# bq25570_board_large.net
KiCad netlist of a schematic drawn in EAGLE
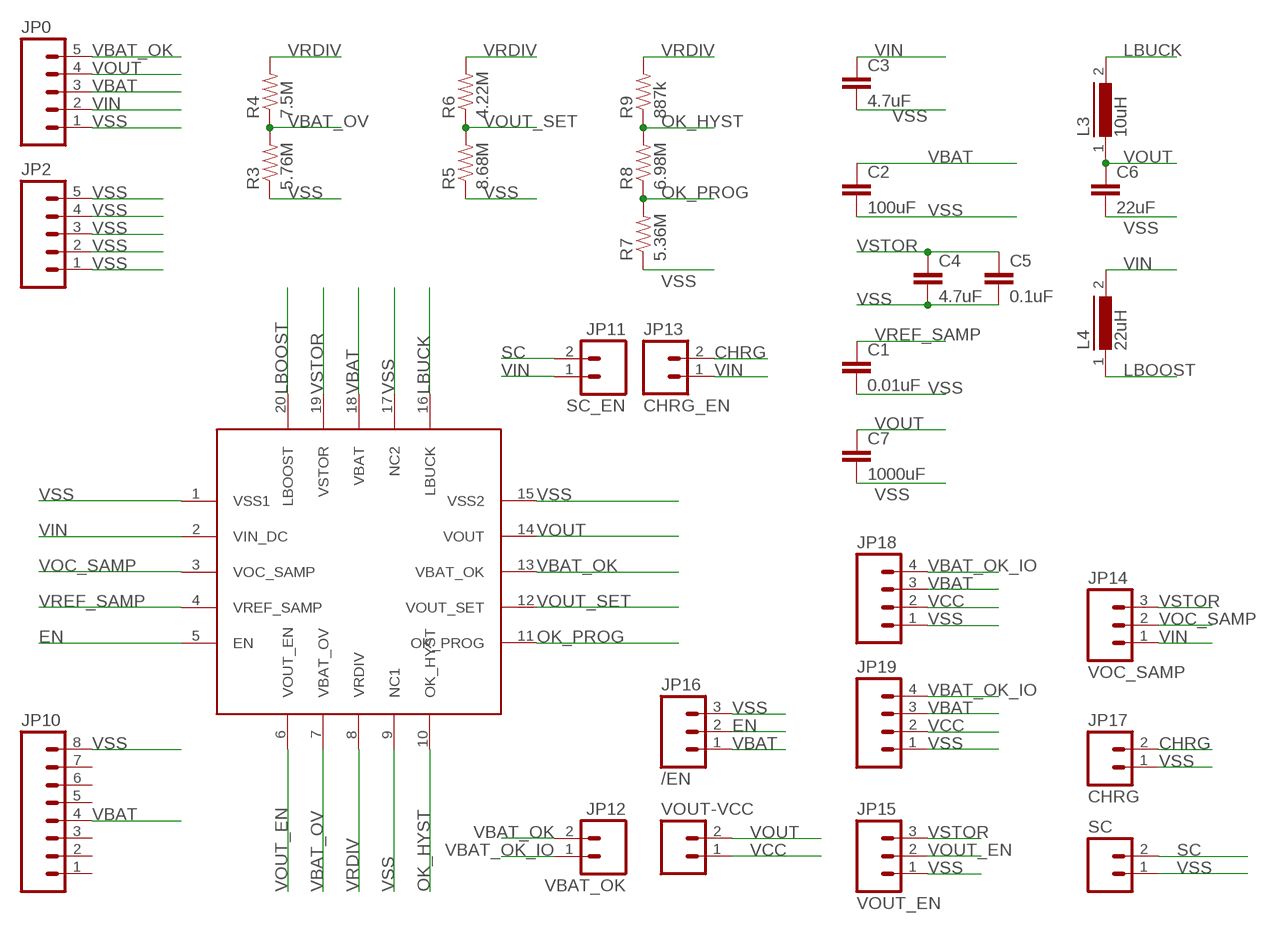
[diagram p0: schematic, sheet 1]

(export (version "E")
  (design (tool "Eeschema 10.0.6"))
  (components
    (comp (ref "C1")
      (value "0.01uF")
      (footprint "eagle-import:CAP-PTH-SMALLEZ")
      (libsource (lib "eagle-import") (part "CAPEZ"))
    )
    (comp (ref "C2")
      (value "100uF")
      (footprint "eagle-import:CAP-PTH-SMALLEZ")
      (libsource (lib "eagle-import") (part "CAPEZ"))
    )
    (comp (ref "C3")
      (value "4.7uF")
      (footprint "eagle-import:CAP-PTH-SMALLEZ")
      (libsource (lib "eagle-import") (part "CAPEZ"))
    )
    (comp (ref "C4")
      (value "4.7uF")
      (footprint "eagle-import:CAP-PTH-SMALLEZ")
      (libsource (lib "eagle-import") (part "CAPEZ"))
    )
    (comp (ref "C5")
      (value "0.1uF")
      (footprint "eagle-import:CAP-PTH-SMALLEZ")
      (libsource (lib "eagle-import") (part "CAPEZ"))
    )
    (comp (ref "C6")
      (value "22uF")
      (footprint "eagle-import:CAP-PTH-SMALLEZ")
      (libsource (lib "eagle-import") (part "CAPEZ"))
    )
    (comp (ref "C7")
      (value "1000uF")
      (footprint "eagle-import:CAP-PTH-SMALLEZ")
      (libsource (lib "eagle-import") (part "CAPEZ"))
    )
    (comp (ref "JP0")
      (value "M05PTH")
      (footprint "eagle-import:1X05")
      (libsource (lib "eagle-import") (part "M05PTH"))
    )
    (comp (ref "JP2")
      (value "M05PTH")
      (footprint "eagle-import:1X05")
      (libsource (lib "eagle-import") (part "M05PTH"))
    )
    (comp (ref "JP10")
      (value "M08")
      (footprint "eagle-import:1X08_ROUND")
      (libsource (lib "eagle-import") (part "M08"))
    )
    (comp (ref "JP11")
      (value "SC_EN")
      (footprint "eagle-import:1X02")
      (libsource (lib "eagle-import") (part "M02PTH"))
    )
    (comp (ref "JP12")
      (value "VBAT_OK")
      (footprint "eagle-import:1X02")
      (libsource (lib "eagle-import") (part "M02PTH"))
    )
    (comp (ref "JP13")
      (value "CHRG_EN")
      (footprint "eagle-import:1X02")
      (libsource (lib "eagle-import") (part "M02PTH"))
    )
    (comp (ref "JP14")
      (value "VOC_SAMP")
      (footprint "eagle-import:1X03")
      (libsource (lib "eagle-import") (part "M03PTH"))
    )
    (comp (ref "JP15")
      (value "VOUT_EN")
      (footprint "eagle-import:1X03")
      (libsource (lib "eagle-import") (part "M03PTH"))
    )
    (comp (ref "JP16")
      (value "/EN")
      (footprint "eagle-import:1X03")
      (libsource (lib "eagle-import") (part "M03PTH"))
    )
    (comp (ref "JP17")
      (value "CHRG")
      (footprint "eagle-import:1X02")
      (libsource (lib "eagle-import") (part "M02PTH"))
    )
    (comp (ref "JP18")
      (value "M04PTH")
      (footprint "eagle-import:1X04")
      (libsource (lib "eagle-import") (part "M04PTH"))
    )
    (comp (ref "JP19")
      (value "M04PTH")
      (footprint "eagle-import:1X04")
      (libsource (lib "eagle-import") (part "M04PTH"))
    )
    (comp (ref "L3")
      (value "10uH")
      (footprint "eagle-import:BC12")
      (libsource (lib "eagle-import") (part "BC12"))
    )
    (comp (ref "L4")
      (value "22uH")
      (footprint "eagle-import:BC12")
      (libsource (lib "eagle-import") (part "BC12"))
    )
    (comp (ref "R3")
      (value "5.76M")
      (footprint "eagle-import:AXIAL-0.3")
      (libsource (lib "eagle-import") (part "1KOHM-1/4W-1%(PTH)"))
    )
    (comp (ref "R4")
      (value "7.5M")
      (footprint "eagle-import:AXIAL-0.3")
      (libsource (lib "eagle-import") (part "1KOHM-1/4W-1%(PTH)"))
    )
    (comp (ref "R5")
      (value "8.68M")
      (footprint "eagle-import:AXIAL-0.3")
      (libsource (lib "eagle-import") (part "1KOHM-1/4W-1%(PTH)"))
    )
    (comp (ref "R6")
      (value "4.22M")
      (footprint "eagle-import:AXIAL-0.3")
      (libsource (lib "eagle-import") (part "1KOHM-1/4W-1%(PTH)"))
    )
    (comp (ref "R7")
      (value "5.36M")
      (footprint "eagle-import:AXIAL-0.3")
      (libsource (lib "eagle-import") (part "1KOHM-1/4W-1%(PTH)"))
    )
    (comp (ref "R8")
      (value "6.98M")
      (footprint "eagle-import:AXIAL-0.3")
      (libsource (lib "eagle-import") (part "1KOHM-1/4W-1%(PTH)"))
    )
    (comp (ref "R9")
      (value "887k")
      (footprint "eagle-import:AXIAL-0.3")
      (libsource (lib "eagle-import") (part "1KOHM-1/4W-1%(PTH)"))
    )
    (comp (ref "SC")
      (value "M02PTH")
      (footprint "eagle-import:1X02")
      (libsource (lib "eagle-import") (part "M02PTH"))
    )
    (comp (ref "SV2")
      (value "BQ25570_BOARD")
      (footprint "eagle-import:MA05-1")
      (libsource (lib "eagle-import") (part "BQ25570_BOARD"))
    )
    (comp (ref "VOUT-VCC")
      (value "M02PTH")
      (footprint "eagle-import:1X02")
      (libsource (lib "eagle-import") (part "M02PTH"))
    )
  )
  (nets
    (net (code "1") (name "/CHRG") (class "Default")
      (node (ref "JP13") (pin "2") (pinfunction "2_2") (pintype "passive"))
      (node (ref "JP17") (pin "2") (pinfunction "2_2") (pintype "passive"))
    )
    (net (code "2") (name "/EN") (class "Default")
      (node (ref "JP16") (pin "2") (pinfunction "2_2") (pintype "passive"))
      (node (ref "SV2") (pin "5") (pinfunction "EN_5") (pintype "bidirectional"))
    )
    (net (code "3") (name "/LBOOST") (class "Default")
      (node (ref "L4") (pin "1") (pinfunction "1_1") (pintype "passive"))
      (node (ref "SV2") (pin "20") (pinfunction "LBOOST_20") (pintype "bidirectional"))
    )
    (net (code "4") (name "/LBUCK") (class "Default")
      (node (ref "L3") (pin "2") (pinfunction "2_2") (pintype "passive"))
      (node (ref "SV2") (pin "16") (pinfunction "LBUCK_16") (pintype "bidirectional"))
    )
    (net (code "5") (name "/OK_HYST") (class "Default")
      (node (ref "R8") (pin "P$2") (pinfunction "2_P$2") (pintype "passive"))
      (node (ref "R9") (pin "P$1") (pinfunction "1_P$1") (pintype "passive"))
      (node (ref "SV2") (pin "10") (pinfunction "OK_HYST_10") (pintype "bidirectional"))
    )
    (net (code "6") (name "/OK_PROG") (class "Default")
      (node (ref "R7") (pin "P$2") (pinfunction "2_P$2") (pintype "passive"))
      (node (ref "R8") (pin "P$1") (pinfunction "1_P$1") (pintype "passive"))
      (node (ref "SV2") (pin "11") (pinfunction "OK_PROG_11") (pintype "bidirectional"))
    )
    (net (code "7") (name "/SC") (class "Default")
      (node (ref "JP11") (pin "2") (pinfunction "2_2") (pintype "passive"))
      (node (ref "SC") (pin "2") (pinfunction "2_2") (pintype "passive"))
    )
    (net (code "8") (name "/VBAT") (class "Default")
      (node (ref "C2") (pin "1") (pinfunction "1_1") (pintype "passive"))
      (node (ref "JP0") (pin "3") (pinfunction "3_3") (pintype "passive"))
      (node (ref "JP10") (pin "4") (pinfunction "4_4") (pintype "passive"))
      (node (ref "JP16") (pin "1") (pinfunction "1_1") (pintype "passive"))
      (node (ref "JP18") (pin "3") (pinfunction "3_3") (pintype "passive"))
      (node (ref "JP19") (pin "3") (pinfunction "3_3") (pintype "passive"))
      (node (ref "SV2") (pin "18") (pinfunction "VBAT_18") (pintype "bidirectional"))
    )
    (net (code "9") (name "/VBAT_OK") (class "Default")
      (node (ref "JP0") (pin "5") (pinfunction "5_5") (pintype "passive"))
      (node (ref "JP12") (pin "2") (pinfunction "2_2") (pintype "passive"))
      (node (ref "SV2") (pin "13") (pinfunction "VBAT_OK_13") (pintype "bidirectional"))
    )
    (net (code "10") (name "/VBAT_OK_IO") (class "Default")
      (node (ref "JP12") (pin "1") (pinfunction "1_1") (pintype "passive"))
      (node (ref "JP18") (pin "4") (pinfunction "4_4") (pintype "passive"))
      (node (ref "JP19") (pin "4") (pinfunction "4_4") (pintype "passive"))
    )
    (net (code "11") (name "/VBAT_OV") (class "Default")
      (node (ref "R3") (pin "P$2") (pinfunction "2_P$2") (pintype "passive"))
      (node (ref "R4") (pin "P$1") (pinfunction "1_P$1") (pintype "passive"))
      (node (ref "SV2") (pin "7") (pinfunction "VBAT_OV_7") (pintype "bidirectional"))
    )
    (net (code "12") (name "/VCC") (class "Default")
      (node (ref "JP18") (pin "2") (pinfunction "2_2") (pintype "passive"))
      (node (ref "JP19") (pin "2") (pinfunction "2_2") (pintype "passive"))
      (node (ref "VOUT-VCC") (pin "1") (pinfunction "1_1") (pintype "passive"))
    )
    (net (code "13") (name "/VIN") (class "Default")
      (node (ref "C3") (pin "1") (pinfunction "1_1") (pintype "passive"))
      (node (ref "JP0") (pin "2") (pinfunction "2_2") (pintype "passive"))
      (node (ref "JP11") (pin "1") (pinfunction "1_1") (pintype "passive"))
      (node (ref "JP13") (pin "1") (pinfunction "1_1") (pintype "passive"))
      (node (ref "JP14") (pin "1") (pinfunction "1_1") (pintype "passive"))
      (node (ref "L4") (pin "2") (pinfunction "2_2") (pintype "passive"))
      (node (ref "SV2") (pin "2") (pinfunction "VIN_DC_2") (pintype "bidirectional"))
    )
    (net (code "14") (name "/VOC_SAMP") (class "Default")
      (node (ref "JP14") (pin "2") (pinfunction "2_2") (pintype "passive"))
      (node (ref "SV2") (pin "3") (pinfunction "VOC_SAMP_3") (pintype "bidirectional"))
    )
    (net (code "15") (name "/VOUT") (class "Default")
      (node (ref "C6") (pin "1") (pinfunction "1_1") (pintype "passive"))
      (node (ref "C7") (pin "1") (pinfunction "1_1") (pintype "passive"))
      (node (ref "JP0") (pin "4") (pinfunction "4_4") (pintype "passive"))
      (node (ref "L3") (pin "1") (pinfunction "1_1") (pintype "passive"))
      (node (ref "SV2") (pin "14") (pinfunction "VOUT_14") (pintype "bidirectional"))
      (node (ref "VOUT-VCC") (pin "2") (pinfunction "2_2") (pintype "passive"))
    )
    (net (code "16") (name "/VOUT_EN") (class "Default")
      (node (ref "JP15") (pin "2") (pinfunction "2_2") (pintype "passive"))
      (node (ref "SV2") (pin "6") (pinfunction "VOUT_EN_6") (pintype "bidirectional"))
    )
    (net (code "17") (name "/VOUT_SET") (class "Default")
      (node (ref "R5") (pin "P$2") (pinfunction "2_P$2") (pintype "passive"))
      (node (ref "R6") (pin "P$1") (pinfunction "1_P$1") (pintype "passive"))
      (node (ref "SV2") (pin "12") (pinfunction "VOUT_SET_12") (pintype "bidirectional"))
    )
    (net (code "18") (name "/VRDIV") (class "Default")
      (node (ref "R4") (pin "P$2") (pinfunction "2_P$2") (pintype "passive"))
      (node (ref "R6") (pin "P$2") (pinfunction "2_P$2") (pintype "passive"))
      (node (ref "R9") (pin "P$2") (pinfunction "2_P$2") (pintype "passive"))
      (node (ref "SV2") (pin "8") (pinfunction "VRDIV_8") (pintype "bidirectional"))
    )
    (net (code "19") (name "/VREF_SAMP") (class "Default")
      (node (ref "C1") (pin "1") (pinfunction "1_1") (pintype "passive"))
      (node (ref "SV2") (pin "4") (pinfunction "VREF_SAMP_4") (pintype "bidirectional"))
    )
    (net (code "20") (name "/VSS") (class "Default")
      (node (ref "C1") (pin "2") (pinfunction "2_2") (pintype "passive"))
      (node (ref "C2") (pin "2") (pinfunction "2_2") (pintype "passive"))
      (node (ref "C3") (pin "2") (pinfunction "2_2") (pintype "passive"))
      (node (ref "C4") (pin "2") (pinfunction "2_2") (pintype "passive"))
      (node (ref "C5") (pin "2") (pinfunction "2_2") (pintype "passive"))
      (node (ref "C6") (pin "2") (pinfunction "2_2") (pintype "passive"))
      (node (ref "C7") (pin "2") (pinfunction "2_2") (pintype "passive"))
      (node (ref "JP0") (pin "1") (pinfunction "1_1") (pintype "passive"))
      (node (ref "JP10") (pin "8") (pinfunction "8_8") (pintype "passive"))
      (node (ref "JP15") (pin "1") (pinfunction "1_1") (pintype "passive"))
      (node (ref "JP16") (pin "3") (pinfunction "3_3") (pintype "passive"))
      (node (ref "JP17") (pin "1") (pinfunction "1_1") (pintype "passive"))
      (node (ref "JP18") (pin "1") (pinfunction "1_1") (pintype "passive"))
      (node (ref "JP19") (pin "1") (pinfunction "1_1") (pintype "passive"))
      (node (ref "JP2") (pin "1") (pinfunction "1_1") (pintype "passive"))
      (node (ref "JP2") (pin "2") (pinfunction "2_2") (pintype "passive"))
      (node (ref "JP2") (pin "3") (pinfunction "3_3") (pintype "passive"))
      (node (ref "JP2") (pin "4") (pinfunction "4_4") (pintype "passive"))
      (node (ref "JP2") (pin "5") (pinfunction "5_5") (pintype "passive"))
      (node (ref "R3") (pin "P$1") (pinfunction "1_P$1") (pintype "passive"))
      (node (ref "R5") (pin "P$1") (pinfunction "1_P$1") (pintype "passive"))
      (node (ref "R7") (pin "P$1") (pinfunction "1_P$1") (pintype "passive"))
      (node (ref "SC") (pin "1") (pinfunction "1_1") (pintype "passive"))
      (node (ref "SV2") (pin "1") (pinfunction "VSS1_1") (pintype "bidirectional"))
      (node (ref "SV2") (pin "15") (pinfunction "VSS2_15") (pintype "bidirectional"))
      (node (ref "SV2") (pin "17") (pinfunction "NC2_17") (pintype "bidirectional"))
      (node (ref "SV2") (pin "9") (pinfunction "NC1_9") (pintype "bidirectional"))
    )
    (net (code "21") (name "/VSTOR") (class "Default")
      (node (ref "C4") (pin "1") (pinfunction "1_1") (pintype "passive"))
      (node (ref "C5") (pin "1") (pinfunction "1_1") (pintype "passive"))
      (node (ref "JP14") (pin "3") (pinfunction "3_3") (pintype "passive"))
      (node (ref "JP15") (pin "3") (pinfunction "3_3") (pintype "passive"))
      (node (ref "SV2") (pin "19") (pinfunction "VSTOR_19") (pintype "bidirectional"))
    )
    (net (code "22") (name "unconnected-(JP10-Pad1)") (class "Default")
      (node (ref "JP10") (pin "1") (pinfunction "1_1") (pintype "passive"))
    )
    (net (code "23") (name "unconnected-(JP10-Pad2)") (class "Default")
      (node (ref "JP10") (pin "2") (pinfunction "2_2") (pintype "passive"))
    )
    (net (code "24") (name "unconnected-(JP10-Pad3)") (class "Default")
      (node (ref "JP10") (pin "3") (pinfunction "3_3") (pintype "passive"))
    )
    (net (code "25") (name "unconnected-(JP10-Pad5)") (class "Default")
      (node (ref "JP10") (pin "5") (pinfunction "5_5") (pintype "passive"))
    )
    (net (code "26") (name "unconnected-(JP10-Pad6)") (class "Default")
      (node (ref "JP10") (pin "6") (pinfunction "6_6") (pintype "passive"))
    )
    (net (code "27") (name "unconnected-(JP10-Pad7)") (class "Default")
      (node (ref "JP10") (pin "7") (pinfunction "7_7") (pintype "passive"))
    )
  )
)
